# Power.net
KiCad netlist of a schematic drawn in Altium Designer
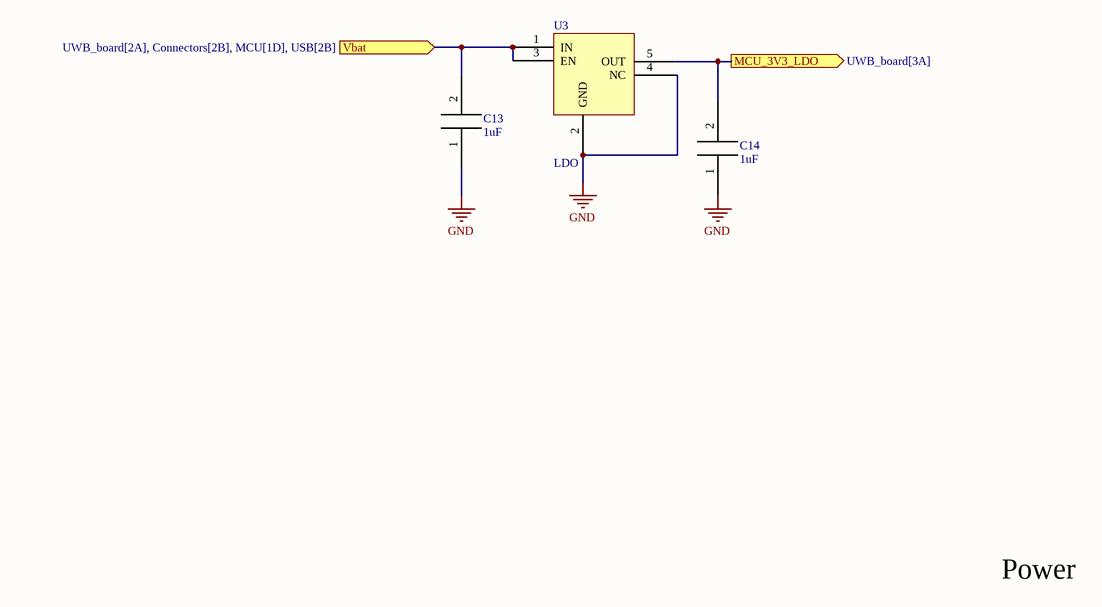
[diagram p0: Power.SchDoc]

(export (version "E")
  (design (tool "Eeschema 10.0.6"))
  (components
    (comp (ref "C13")
      (value "1uF")
      (footprint "0603_cap")
      (description "1uF 50V X5R ±10% 0603 Multilayer Ceramic Capacitors MLCC - SMD/SMT ROHS")
      (fields (field (name "LCSC PART #") "C15849"))
      (libsource (lib "Schlib1") (part "CL10A105KB8NNNC"))
    )
    (comp (ref "C14")
      (value "1uF")
      (footprint "0603_cap")
      (description "1uF 50V X5R ±10% 0603 Multilayer Ceramic Capacitors MLCC - SMD/SMT ROHS")
      (fields (field (name "LCSC PART #") "C15849"))
      (libsource (lib "Schlib1") (part "CL10A105KB8NNNC"))
    )
    (comp (ref "U3")
      (value "LDO")
      (footprint "SOT95P280X145-5N")
      (fields (field (name "LCSC PART #") "C2862740"))
      (libsource (lib "Schlib1") (part "TPS7A20"))
    )
  )
  (nets
    (net (code "1") (name "/MCU_3V3_LDO") (class "Default")
      (node (ref "C14") (pin "2") (pinfunction "3_2") (pintype "passive"))
      (node (ref "U3") (pin "5") (pinfunction "OUT_5") (pintype "power_in"))
    )
    (net (code "2") (name "/Vbat") (class "Default")
      (node (ref "C13") (pin "2") (pinfunction "3_2") (pintype "passive"))
      (node (ref "U3") (pin "1") (pinfunction "IN_1") (pintype "power_in"))
      (node (ref "U3") (pin "3") (pinfunction "EN_3") (pintype "power_in"))
    )
    (net (code "3") (name "GND") (class "Default")
      (node (ref "C13") (pin "1") (pintype "passive"))
      (node (ref "C14") (pin "1") (pintype "passive"))
      (node (ref "U3") (pin "2") (pinfunction "GND_2") (pintype "power_in"))
      (node (ref "U3") (pin "4") (pinfunction "NC_4") (pintype "power_in"))
    )
  )
)
